# driver2.net
KiCad netlist of a schematic drawn in EAGLE
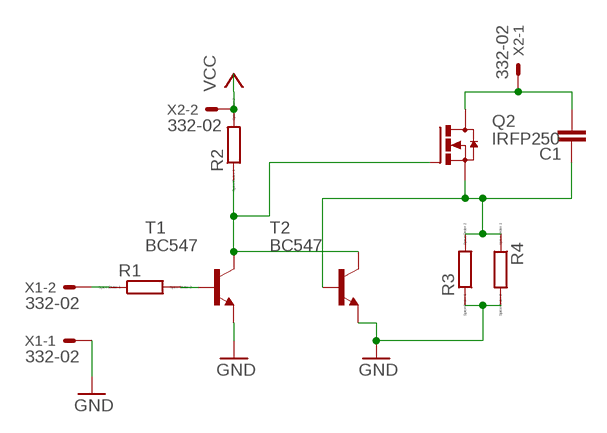
[diagram p0: schematic, sheet 1]

(export (version "E")
  (design (tool "Eeschema 10.0.6"))
  (components
    (comp (ref "C1")
      (value "C-EU025-025X050")
      (footprint "eagle-import:C025-025X050")
      (libsource (lib "eagle-import") (part "C-EU025-025X050"))
    )
    (comp (ref "Q2")
      (value "IRFP250")
      (footprint "eagle-import:TO-247AD-V")
      (libsource (lib "eagle-import") (part "IRFP250"))
    )
    (comp (ref "R1")
      (value "R0204/7")
      (footprint "eagle-import:0204_7")
      (libsource (lib "eagle-import") (part "R0204/7"))
    )
    (comp (ref "R2")
      (value "R0204/7")
      (footprint "eagle-import:0204_7")
      (libsource (lib "eagle-import") (part "R0204/7"))
    )
    (comp (ref "R3")
      (value "R0204/7")
      (footprint "eagle-import:0204_7")
      (libsource (lib "eagle-import") (part "R0204/7"))
    )
    (comp (ref "R4")
      (value "R0204/7")
      (footprint "eagle-import:0204_7")
      (libsource (lib "eagle-import") (part "R0204/7"))
    )
    (comp (ref "T1")
      (value "BC547")
      (footprint "eagle-import:TO92")
      (libsource (lib "eagle-import") (part "BC547"))
    )
    (comp (ref "T2")
      (value "BC547")
      (footprint "eagle-import:TO92")
      (libsource (lib "eagle-import") (part "BC547"))
    )
    (comp (ref "X1")
      (value "332-02")
      (footprint "eagle-import:332-02")
      (libsource (lib "eagle-import") (part "332-02"))
    )
    (comp (ref "X2")
      (value "332-02")
      (footprint "eagle-import:332-02")
      (libsource (lib "eagle-import") (part "332-02"))
    )
  )
  (nets
    (net (code "1") (name "GND") (class "Default")
      (node (ref "R3") (pin "1") (pinfunction "1_1") (pintype "passive"))
      (node (ref "R4") (pin "2") (pinfunction "2_2") (pintype "passive"))
      (node (ref "T1") (pin "1") (pinfunction "E_1") (pintype "passive"))
      (node (ref "T2") (pin "1") (pinfunction "E_1") (pintype "passive"))
      (node (ref "X1") (pin "1") (pinfunction "S_1") (pintype "passive"))
    )
    (net (code "2") (name "Net-(T1-B)") (class "Default")
      (node (ref "R1") (pin "2") (pinfunction "2_2") (pintype "passive"))
      (node (ref "T1") (pin "2") (pinfunction "B_2") (pintype "passive"))
    )
    (net (code "3") (name "Net-(T1-C)") (class "Default")
      (node (ref "Q2") (pin "G") (pinfunction "G_G") (pintype "passive"))
      (node (ref "R2") (pin "1") (pinfunction "1_1") (pintype "passive"))
      (node (ref "T1") (pin "3") (pinfunction "C_3") (pintype "passive"))
      (node (ref "T2") (pin "3") (pinfunction "C_3") (pintype "passive"))
    )
    (net (code "4") (name "Net-(T2-B)") (class "Default")
      (node (ref "C1") (pin "1") (pinfunction "1_1") (pintype "passive"))
      (node (ref "Q2") (pin "S") (pinfunction "S_S") (pintype "passive"))
      (node (ref "R3") (pin "2") (pinfunction "2_2") (pintype "passive"))
      (node (ref "R4") (pin "1") (pinfunction "1_1") (pintype "passive"))
      (node (ref "T2") (pin "2") (pinfunction "B_2") (pintype "passive"))
    )
    (net (code "5") (name "Net-(X1B-S)") (class "Default")
      (node (ref "R1") (pin "1") (pinfunction "1_1") (pintype "passive"))
      (node (ref "X1") (pin "2") (pinfunction "S_2") (pintype "passive"))
    )
    (net (code "6") (name "Net-(X2A-S)") (class "Default")
      (node (ref "C1") (pin "2") (pinfunction "2_2") (pintype "passive"))
      (node (ref "Q2") (pin "D") (pinfunction "D_D") (pintype "passive"))
      (node (ref "X2") (pin "1") (pinfunction "S_1") (pintype "passive"))
    )
    (net (code "7") (name "VCC") (class "Default")
      (node (ref "R2") (pin "2") (pinfunction "2_2") (pintype "passive"))
      (node (ref "X2") (pin "2") (pinfunction "S_2") (pintype "passive"))
    )
  )
)
